# Project_Hackathon_PCB.net
KiCad netlist of a schematic drawn in EasyEDA Pro
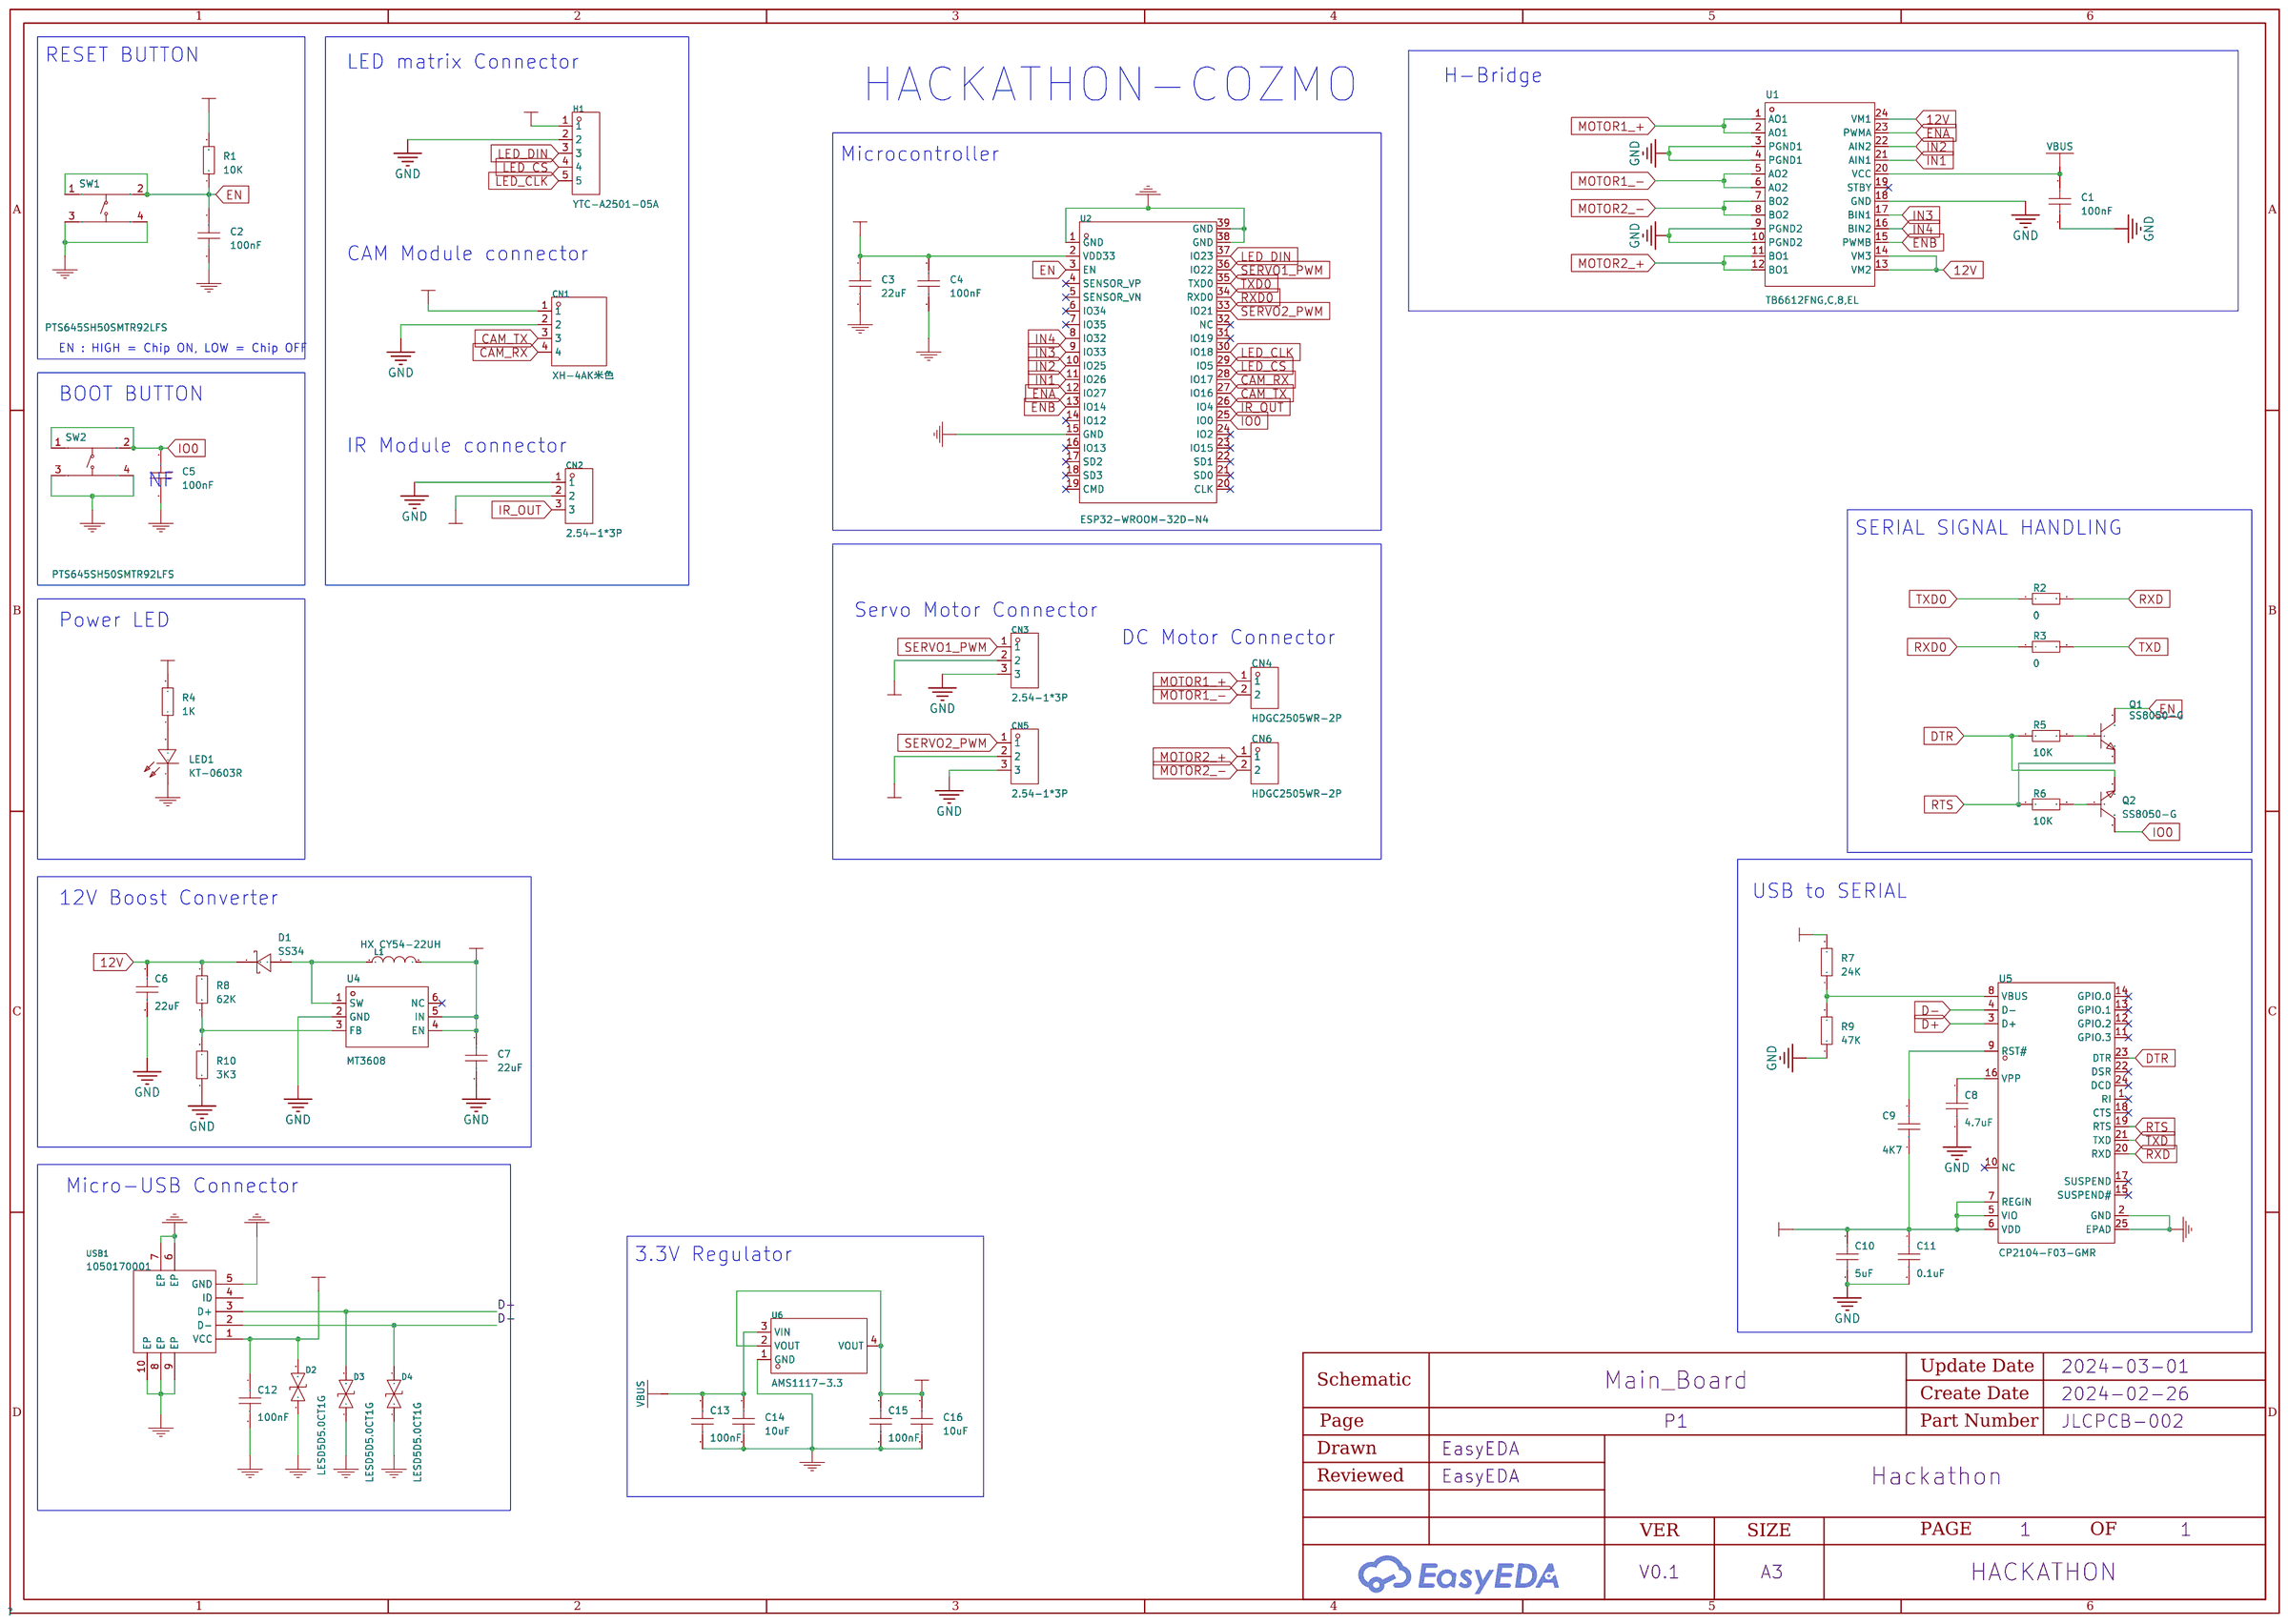
[diagram p0: schematic sheet]

(export (version "E")
  (design (tool "Eeschema 10.0.6"))
  (components
    (comp (ref "C1")
      (value "100nF")
      (footprint "easyedapro:C0603")
      (libsource (lib "easyedapro") (part "CAP"))
    )
    (comp (ref "C2")
      (value "100nF")
      (footprint "easyedapro:C0603")
      (libsource (lib "easyedapro") (part "CAP"))
    )
    (comp (ref "C3")
      (value "22uF")
      (footprint "easyedapro:C0603")
      (libsource (lib "easyedapro") (part "CAP"))
    )
    (comp (ref "C4")
      (value "100nF")
      (footprint "easyedapro:C0603")
      (libsource (lib "easyedapro") (part "CAP"))
    )
    (comp (ref "C5")
      (value "100nF")
      (footprint "easyedapro:C0603")
      (libsource (lib "easyedapro") (part "CAP"))
    )
    (comp (ref "C6")
      (value "22uF")
      (footprint "easyedapro:C0603")
      (libsource (lib "easyedapro") (part "CAP"))
    )
    (comp (ref "C7")
      (value "22uF")
      (footprint "easyedapro:C0603")
      (libsource (lib "easyedapro") (part "CAP"))
    )
    (comp (ref "C8")
      (value "4.7uF")
      (footprint "easyedapro:C0603")
      (libsource (lib "easyedapro") (part "CAP"))
    )
    (comp (ref "C9") (value "4K7") (footprint "easyedapro:C0603") (libsource (lib "easyedapro") (part "CAP")))
    (comp (ref "C10")
      (value "5uF")
      (footprint "easyedapro:C0603")
      (libsource (lib "easyedapro") (part "CAP"))
    )
    (comp (ref "C11")
      (value "0.1uF")
      (footprint "easyedapro:C0603")
      (libsource (lib "easyedapro") (part "CAP"))
    )
    (comp (ref "C12")
      (value "100nF")
      (footprint "easyedapro:C0603")
      (libsource (lib "easyedapro") (part "CAP"))
    )
    (comp (ref "C13")
      (value "100nF")
      (footprint "easyedapro:C0603")
      (libsource (lib "easyedapro") (part "CAP"))
    )
    (comp (ref "C14")
      (value "10uF")
      (footprint "easyedapro:C0603")
      (libsource (lib "easyedapro") (part "CAP"))
    )
    (comp (ref "C15")
      (value "100nF")
      (footprint "easyedapro:C0603")
      (libsource (lib "easyedapro") (part "CAP"))
    )
    (comp (ref "C16")
      (value "10uF")
      (footprint "easyedapro:C0603")
      (libsource (lib "easyedapro") (part "CAP"))
    )
    (comp (ref "CN1")
      (value "XH-4AK米色")
      (footprint "easyedapro:CONN-TH_4P-P2.50_XH-4A")
      (fields (field (name "Manufacturer") "BOOMELE(博穆精密)"))
      (libsource (lib "easyedapro") (part "XH-4AK M"))
    )
    (comp (ref "CN2")
      (value "2.54-1*3P")
      (footprint "easyedapro:CONN-TH_C722693")
      (fields (field (name "Manufacturer") "CAX(创都)"))
      (libsource (lib "easyedapro") (part "2.54-1*3P"))
    )
    (comp (ref "CN3")
      (value "2.54-1*3P")
      (footprint "easyedapro:CONN-TH_C722693")
      (fields (field (name "Manufacturer") "CAX(创都)"))
      (libsource (lib "easyedapro") (part "2.54-1*3P"))
    )
    (comp (ref "CN4")
      (value "HDGC2505WR-2P")
      (footprint "easyedapro:CONN-TH_HDGC2505WR-2P")
      (fields (field (name "Manufacturer") "HDGC(华德共创)"))
      (libsource (lib "easyedapro") (part "HDGC2505WR-2P"))
    )
    (comp (ref "CN5")
      (value "2.54-1*3P")
      (footprint "easyedapro:CONN-TH_C722693")
      (fields (field (name "Manufacturer") "CAX(创都)"))
      (libsource (lib "easyedapro") (part "2.54-1*3P"))
    )
    (comp (ref "CN6")
      (value "HDGC2505WR-2P")
      (footprint "easyedapro:CONN-TH_HDGC2505WR-2P")
      (fields (field (name "Manufacturer") "HDGC(华德共创)"))
      (libsource (lib "easyedapro") (part "HDGC2505WR-2P"))
    )
    (comp (ref "D1")
      (value "SS34")
      (footprint "easyedapro:SMC_L6.9-W5.9-LS7.9-RD")
      (description "Forward Voltage (Vf@If):500mV@3A Reverse Voltage (Vr):40V Average Rectified Current (Io):3A")
      (libsource (lib "easyedapro") (part "SS34_C169162"))
    )
    (comp (ref "D2")
      (value "LESD5D5.0CT1G")
      (footprint "easyedapro:SOD-523_L1.2-W0.8-LS1.6-BI")
      (fields (field (name "Manufacturer") "LRC(乐山无线电)"))
      (libsource (lib "easyedapro") (part "LESD5D5.0CT1G"))
    )
    (comp (ref "D3")
      (value "LESD5D5.0CT1G")
      (footprint "easyedapro:SOD-523_L1.2-W0.8-LS1.6-BI")
      (fields (field (name "Manufacturer") "LRC(乐山无线电)"))
      (libsource (lib "easyedapro") (part "LESD5D5.0CT1G"))
    )
    (comp (ref "D4")
      (value "LESD5D5.0CT1G")
      (footprint "easyedapro:SOD-523_L1.2-W0.8-LS1.6-BI")
      (fields (field (name "Manufacturer") "LRC(乐山无线电)"))
      (libsource (lib "easyedapro") (part "LESD5D5.0CT1G"))
    )
    (comp (ref "H1")
      (value "YTC-A2501-05A")
      (footprint "easyedapro:HDR-TH_5P-P2.50-V-F-2")
      (fields (field (name "Manufacturer") "YIYUAN(怡远)"))
      (libsource (lib "easyedapro") (part "YTC-A2501-05A"))
    )
    (comp (ref "L1")
      (value "HX CY54-22UH")
      (footprint "easyedapro:IND-SMD_L5.8-W5.2_SLF05XX")
      (fields (field (name "Manufacturer") "hanxia(韩下)"))
      (libsource (lib "easyedapro") (part "HX CY54-22UH"))
    )
    (comp (ref "LED1")
      (value "KT-0603R")
      (footprint "easyedapro:LED0603-RD")
      (fields (field (name "Manufacturer") "KENTO"))
      (libsource (lib "easyedapro") (part "KT-0603R"))
    )
    (comp (ref "Q1")
      (value "SS8050-G")
      (footprint "easyedapro:SOT-23-3_L2.9-W1.3-P1.90-LS2.4-BR")
      (fields (field (name "Manufacturer") "CJ(江苏长电/长晶)"))
      (libsource (lib "easyedapro") (part "SS8050-G_C164885"))
    )
    (comp (ref "Q2")
      (value "SS8050-G")
      (footprint "easyedapro:SOT-23-3_L2.9-W1.3-P1.90-LS2.4-BR")
      (fields (field (name "Manufacturer") "CJ(江苏长电/长晶)"))
      (libsource (lib "easyedapro") (part "SS8050-G_C164885"))
    )
    (comp (ref "R1") (value "10K") (footprint "easyedapro:R0603") (libsource (lib "easyedapro") (part "Res")))
    (comp (ref "R2") (value "0") (footprint "easyedapro:R0603") (libsource (lib "easyedapro") (part "Res")))
    (comp (ref "R3") (value "0") (footprint "easyedapro:R0603") (libsource (lib "easyedapro") (part "Res")))
    (comp (ref "R4") (value "1K") (footprint "easyedapro:R0603") (libsource (lib "easyedapro") (part "Res")))
    (comp (ref "R5") (value "10K") (footprint "easyedapro:R0603") (libsource (lib "easyedapro") (part "Res")))
    (comp (ref "R6") (value "10K") (footprint "easyedapro:R0603") (libsource (lib "easyedapro") (part "Res")))
    (comp (ref "R7") (value "24K") (footprint "easyedapro:R0603") (libsource (lib "easyedapro") (part "Res")))
    (comp (ref "R8") (value "62K") (footprint "easyedapro:R0603") (libsource (lib "easyedapro") (part "Res")))
    (comp (ref "R9") (value "47K") (footprint "easyedapro:R0603") (libsource (lib "easyedapro") (part "Res")))
    (comp (ref "R10")
      (value "3K3")
      (footprint "easyedapro:R0603")
      (libsource (lib "easyedapro") (part "Res"))
    )
    (comp (ref "SW1")
      (value "PTS645SH50SMTR92LFS")
      (footprint "easyedapro:KEY-SMD_4P-L6.0-W6.0-P4.50-LS9.0")
      (fields (field (name "Manufacturer") "C&K"))
      (libsource (lib "easyedapro") (part "PTS645SH50SMTR92LFS"))
    )
    (comp (ref "SW2")
      (value "PTS645SH50SMTR92LFS")
      (footprint "easyedapro:KEY-SMD_4P-L6.0-W6.0-P4.50-LS9.0")
      (fields (field (name "Manufacturer") "C&K"))
      (libsource (lib "easyedapro") (part "PTS645SH50SMTR92LFS"))
    )
    (comp (ref "U1")
      (value "TB6612FNG,C,8,EL")
      (footprint "easyedapro:SSOP-24_L8.3-W5.6-P0.65-LS7.6-BL")
      (fields (field (name "Manufacturer") "TOSHIBA(东芝)"))
      (libsource (lib "easyedapro") (part "TB6612FNG,C,8,EL"))
    )
    (comp (ref "U2")
      (value "ESP32-WROOM-32D-N4")
      (footprint "easyedapro:WIFIM-SMD_39P-L25.5-W18.0-P1.27-BL")
      (fields (field (name "Manufacturer") "ESPRESSIF(乐鑫)"))
      (libsource (lib "easyedapro") (part "ESP32-WROOM-32D"))
    )
    (comp (ref "U4")
      (value "MT3608")
      (footprint "easyedapro:SOT-23-6_L2.9-W1.6-P0.95-LS2.8-BL")
      (fields (field (name "Manufacturer") "西安航天民芯"))
      (libsource (lib "easyedapro") (part "MT3608"))
    )
    (comp (ref "U5")
      (value "CP2104-F03-GMR")
      (footprint "easyedapro:QFN-24_L4.0-W4.0-P0.50-BL-EP2.7")
      (fields (field (name "Manufacturer") "SKYWORKS/SILICON LABS(芯科)"))
      (libsource (lib "easyedapro") (part "CP2104-F03-GM"))
    )
    (comp (ref "U6")
      (value "AMS1117-3.3")
      (footprint "easyedapro:SOT-223-3_L6.5-W3.4-P2.30-LS7.0-BR")
      (fields (field (name "Manufacturer") "AMS"))
      (libsource (lib "easyedapro") (part "AMS1117-3.3"))
    )
    (comp (ref "USB1")
      (value "1050170001")
      (footprint "easyedapro:MICRO-USB-SMD_105017-0001")
      (fields (field (name "Manufacturer") "MOLEX"))
      (libsource (lib "easyedapro") (part "105017-0001"))
    )
  )
  (nets
    (net (code "1") (name "+3V3") (class "Default")
      (node (ref "C10") (pin "1") (pinfunction "1_1") (pintype "input"))
      (node (ref "C11") (pin "1") (pinfunction "1_1") (pintype "input"))
      (node (ref "C15") (pin "1") (pinfunction "1_1") (pintype "input"))
      (node (ref "C16") (pin "1") (pinfunction "1_1") (pintype "input"))
      (node (ref "C3") (pin "1") (pinfunction "1_1") (pintype "input"))
      (node (ref "C4") (pin "1") (pinfunction "1_1") (pintype "input"))
      (node (ref "C9") (pin "1") (pinfunction "1_1") (pintype "input"))
      (node (ref "H1") (pin "1") (pinfunction "1_1") (pintype "input"))
      (node (ref "R1") (pin "2") (pinfunction "2_2") (pintype "input"))
      (node (ref "R4") (pin "2") (pinfunction "2_2") (pintype "input"))
      (node (ref "U2") (pin "2") (pinfunction "VDD33_2") (pintype "input"))
      (node (ref "U5") (pin "5") (pinfunction "VIO_5") (pintype "unspecified"))
      (node (ref "U5") (pin "6") (pinfunction "VDD_6") (pintype "unspecified"))
      (node (ref "U5") (pin "7") (pinfunction "REGIN_7") (pintype "unspecified"))
      (node (ref "U6") (pin "2") (pinfunction "VOUT_2") (pintype "input"))
      (node (ref "U6") (pin "4") (pinfunction "VOUT_4") (pintype "input"))
    )
    (net (code "2") (name "12V") (class "Default")
      (node (ref "C6") (pin "1") (pinfunction "1_1") (pintype "input"))
      (node (ref "D1") (pin "1") (pinfunction "C_1") (pintype "input"))
      (node (ref "R8") (pin "2") (pinfunction "2_2") (pintype "input"))
      (node (ref "U1") (pin "13") (pinfunction "VM2_13") (pintype "input"))
      (node (ref "U1") (pin "14") (pinfunction "VM3_14") (pintype "input"))
      (node (ref "U1") (pin "24") (pinfunction "VM1_24") (pintype "input"))
    )
    (net (code "3") (name "CAM_RX") (class "Default")
      (node (ref "CN1") (pin "4") (pinfunction "4_4") (pintype "input"))
      (node (ref "U2") (pin "28") (pinfunction "IO17_28") (pintype "input"))
    )
    (net (code "4") (name "CAM_TX") (class "Default")
      (node (ref "CN1") (pin "3") (pinfunction "3_3") (pintype "input"))
      (node (ref "U2") (pin "27") (pinfunction "IO16_27") (pintype "input"))
    )
    (net (code "5") (name "D+") (class "Default")
      (node (ref "D3") (pin "2") (pinfunction "2_2") (pintype "input"))
      (node (ref "U5") (pin "3") (pinfunction "D+_3") (pintype "unspecified"))
      (node (ref "USB1") (pin "3") (pinfunction "D+_3") (pintype "input"))
    )
    (net (code "6") (name "D-") (class "Default")
      (node (ref "D4") (pin "2") (pinfunction "2_2") (pintype "input"))
      (node (ref "U5") (pin "4") (pinfunction "D-_4") (pintype "unspecified"))
      (node (ref "USB1") (pin "2") (pinfunction "D-_2") (pintype "input"))
    )
    (net (code "7") (name "DTR") (class "Default")
      (node (ref "Q2") (pin "2") (pinfunction "E_2") (pintype "unspecified"))
      (node (ref "R5") (pin "1") (pinfunction "1_1") (pintype "input"))
      (node (ref "U5") (pin "23") (pinfunction "DTR_23") (pintype "unspecified"))
    )
    (net (code "8") (name "EN") (class "Default")
      (node (ref "C2") (pin "1") (pinfunction "1_1") (pintype "input"))
      (node (ref "Q1") (pin "3") (pinfunction "C_3") (pintype "unspecified"))
      (node (ref "R1") (pin "1") (pinfunction "1_1") (pintype "input"))
      (node (ref "SW1") (pin "1") (pinfunction "1_1") (pintype "input"))
      (node (ref "SW1") (pin "2") (pinfunction "2_2") (pintype "input"))
      (node (ref "U2") (pin "3") (pinfunction "EN_3") (pintype "input"))
    )
    (net (code "9") (name "ENA") (class "Default")
      (node (ref "U1") (pin "23") (pinfunction "PWMA_23") (pintype "input"))
      (node (ref "U2") (pin "12") (pinfunction "IO27_12") (pintype "input"))
    )
    (net (code "10") (name "ENB") (class "Default")
      (node (ref "U1") (pin "15") (pinfunction "PWMB_15") (pintype "input"))
      (node (ref "U2") (pin "13") (pinfunction "IO14_13") (pintype "input"))
    )
    (net (code "11") (name "GND") (class "Default")
      (node (ref "C1") (pin "2") (pinfunction "2_2") (pintype "input"))
      (node (ref "C10") (pin "2") (pinfunction "2_2") (pintype "input"))
      (node (ref "C11") (pin "2") (pinfunction "2_2") (pintype "input"))
      (node (ref "C12") (pin "2") (pinfunction "2_2") (pintype "input"))
      (node (ref "C13") (pin "2") (pinfunction "2_2") (pintype "input"))
      (node (ref "C14") (pin "2") (pinfunction "2_2") (pintype "input"))
      (node (ref "C15") (pin "2") (pinfunction "2_2") (pintype "input"))
      (node (ref "C16") (pin "2") (pinfunction "2_2") (pintype "input"))
      (node (ref "C2") (pin "2") (pinfunction "2_2") (pintype "input"))
      (node (ref "C3") (pin "2") (pinfunction "2_2") (pintype "input"))
      (node (ref "C4") (pin "2") (pinfunction "2_2") (pintype "input"))
      (node (ref "C5") (pin "2") (pinfunction "2_2") (pintype "input"))
      (node (ref "C6") (pin "2") (pinfunction "2_2") (pintype "input"))
      (node (ref "C7") (pin "2") (pinfunction "2_2") (pintype "input"))
      (node (ref "C8") (pin "2") (pinfunction "2_2") (pintype "input"))
      (node (ref "CN1") (pin "2") (pinfunction "2_2") (pintype "input"))
      (node (ref "CN2") (pin "1") (pinfunction "1_1") (pintype "input"))
      (node (ref "CN3") (pin "3") (pinfunction "3_3") (pintype "input"))
      (node (ref "CN5") (pin "3") (pinfunction "3_3") (pintype "input"))
      (node (ref "D2") (pin "1") (pinfunction "1_1") (pintype "input"))
      (node (ref "D3") (pin "1") (pinfunction "1_1") (pintype "input"))
      (node (ref "D4") (pin "1") (pinfunction "1_1") (pintype "input"))
      (node (ref "H1") (pin "2") (pinfunction "2_2") (pintype "input"))
      (node (ref "LED1") (pin "1") (pinfunction "K_1") (pintype "input"))
      (node (ref "R10") (pin "1") (pinfunction "1_1") (pintype "input"))
      (node (ref "R9") (pin "1") (pinfunction "1_1") (pintype "input"))
      (node (ref "SW1") (pin "3") (pinfunction "3_3") (pintype "input"))
      (node (ref "SW1") (pin "4") (pinfunction "4_4") (pintype "input"))
      (node (ref "SW2") (pin "3") (pinfunction "3_3") (pintype "input"))
      (node (ref "SW2") (pin "4") (pinfunction "4_4") (pintype "input"))
      (node (ref "U1") (pin "10") (pinfunction "PGND2_10") (pintype "input"))
      (node (ref "U1") (pin "18") (pinfunction "GND_18") (pintype "input"))
      (node (ref "U1") (pin "3") (pinfunction "PGND1_3") (pintype "input"))
      (node (ref "U1") (pin "4") (pinfunction "PGND1_4") (pintype "input"))
      (node (ref "U1") (pin "9") (pinfunction "PGND2_9") (pintype "input"))
      (node (ref "U2") (pin "1") (pinfunction "GND_1") (pintype "input"))
      (node (ref "U2") (pin "15") (pinfunction "GND_15") (pintype "input"))
      (node (ref "U2") (pin "38") (pinfunction "GND_38") (pintype "input"))
      (node (ref "U2") (pin "39") (pinfunction "GND_39") (pintype "input"))
      (node (ref "U4") (pin "2") (pinfunction "GND_2") (pintype "input"))
      (node (ref "U5") (pin "2") (pinfunction "GND_2") (pintype "unspecified"))
      (node (ref "U5") (pin "25") (pinfunction "EPAD_25") (pintype "unspecified"))
      (node (ref "U6") (pin "1") (pinfunction "GND_1") (pintype "input"))
      (node (ref "USB1") (pin "10") (pinfunction "EP_10") (pintype "input"))
      (node (ref "USB1") (pin "5") (pinfunction "GND_5") (pintype "input"))
      (node (ref "USB1") (pin "6") (pinfunction "EP_6") (pintype "input"))
      (node (ref "USB1") (pin "7") (pinfunction "EP_7") (pintype "input"))
      (node (ref "USB1") (pin "8") (pinfunction "EP_8") (pintype "input"))
      (node (ref "USB1") (pin "9") (pinfunction "EP_9") (pintype "input"))
    )
    (net (code "12") (name "IN1") (class "Default")
      (node (ref "U1") (pin "21") (pinfunction "AIN1_21") (pintype "input"))
      (node (ref "U2") (pin "11") (pinfunction "IO26_11") (pintype "input"))
    )
    (net (code "13") (name "IN2") (class "Default")
      (node (ref "U1") (pin "22") (pinfunction "AIN2_22") (pintype "input"))
      (node (ref "U2") (pin "10") (pinfunction "IO25_10") (pintype "input"))
    )
    (net (code "14") (name "IN3") (class "Default")
      (node (ref "U1") (pin "17") (pinfunction "BIN1_17") (pintype "input"))
      (node (ref "U2") (pin "9") (pinfunction "IO33_9") (pintype "input"))
    )
    (net (code "15") (name "IN4") (class "Default")
      (node (ref "U1") (pin "16") (pinfunction "BIN2_16") (pintype "input"))
      (node (ref "U2") (pin "8") (pinfunction "IO32_8") (pintype "input"))
    )
    (net (code "16") (name "IO0") (class "Default")
      (node (ref "C5") (pin "1") (pinfunction "1_1") (pintype "input"))
      (node (ref "Q2") (pin "3") (pinfunction "C_3") (pintype "unspecified"))
      (node (ref "SW2") (pin "1") (pinfunction "1_1") (pintype "input"))
      (node (ref "SW2") (pin "2") (pinfunction "2_2") (pintype "input"))
      (node (ref "U2") (pin "25") (pinfunction "IO0_25") (pintype "input"))
    )
    (net (code "17") (name "IR_OUT") (class "Default")
      (node (ref "CN2") (pin "3") (pinfunction "3_3") (pintype "input"))
      (node (ref "U2") (pin "26") (pinfunction "IO4_26") (pintype "input"))
    )
    (net (code "18") (name "LED_CLK") (class "Default")
      (node (ref "H1") (pin "5") (pinfunction "5_5") (pintype "input"))
      (node (ref "U2") (pin "30") (pinfunction "IO18_30") (pintype "input"))
    )
    (net (code "19") (name "LED_CS") (class "Default")
      (node (ref "H1") (pin "4") (pinfunction "4_4") (pintype "input"))
      (node (ref "U2") (pin "29") (pinfunction "IO5_29") (pintype "input"))
    )
    (net (code "20") (name "LED_DIN") (class "Default")
      (node (ref "H1") (pin "3") (pinfunction "3_3") (pintype "input"))
      (node (ref "U2") (pin "37") (pinfunction "IO23_37") (pintype "input"))
    )
    (net (code "21") (name "MOTOR1_+") (class "Default")
      (node (ref "CN4") (pin "1") (pinfunction "1_1") (pintype "unspecified"))
      (node (ref "U1") (pin "1") (pinfunction "AO1_1") (pintype "input"))
      (node (ref "U1") (pin "2") (pinfunction "AO1_2") (pintype "input"))
    )
    (net (code "22") (name "MOTOR1_-") (class "Default")
      (node (ref "CN4") (pin "2") (pinfunction "2_2") (pintype "unspecified"))
      (node (ref "U1") (pin "5") (pinfunction "AO2_5") (pintype "input"))
      (node (ref "U1") (pin "6") (pinfunction "AO2_6") (pintype "input"))
    )
    (net (code "23") (name "MOTOR2_+") (class "Default")
      (node (ref "CN6") (pin "1") (pinfunction "1_1") (pintype "unspecified"))
      (node (ref "U1") (pin "11") (pinfunction "BO1_11") (pintype "input"))
      (node (ref "U1") (pin "12") (pinfunction "BO1_12") (pintype "input"))
    )
    (net (code "24") (name "MOTOR2_-") (class "Default")
      (node (ref "CN6") (pin "2") (pinfunction "2_2") (pintype "unspecified"))
      (node (ref "U1") (pin "7") (pinfunction "BO2_7") (pintype "input"))
      (node (ref "U1") (pin "8") (pinfunction "BO2_8") (pintype "input"))
    )
    (net (code "25") (name "Net-(D1-A)") (class "Default")
      (node (ref "D1") (pin "2") (pinfunction "A_2") (pintype "input"))
      (node (ref "L1") (pin "1") (pinfunction "1_1") (pintype "input"))
      (node (ref "U4") (pin "1") (pinfunction "SW_1") (pintype "input"))
    )
    (net (code "26") (name "Net-(LED1-A)") (class "Default")
      (node (ref "LED1") (pin "2") (pinfunction "A_2") (pintype "input"))
      (node (ref "R4") (pin "1") (pinfunction "1_1") (pintype "input"))
    )
    (net (code "27") (name "Net-(Q1-B)") (class "Default")
      (node (ref "Q1") (pin "1") (pinfunction "B_1") (pintype "unspecified"))
      (node (ref "R5") (pin "2") (pinfunction "2_2") (pintype "input"))
    )
    (net (code "28") (name "Net-(Q2-B)") (class "Default")
      (node (ref "Q2") (pin "1") (pinfunction "B_1") (pintype "unspecified"))
      (node (ref "R6") (pin "2") (pinfunction "2_2") (pintype "input"))
    )
    (net (code "29") (name "Net-(U4-FB)") (class "Default")
      (node (ref "R10") (pin "2") (pinfunction "2_2") (pintype "input"))
      (node (ref "R8") (pin "1") (pinfunction "1_1") (pintype "input"))
      (node (ref "U4") (pin "3") (pinfunction "FB_3") (pintype "input"))
    )
    (net (code "30") (name "Net-(U5-RST#)") (class "Default")
      (node (ref "C9") (pin "2") (pinfunction "2_2") (pintype "input"))
      (node (ref "U5") (pin "9") (pinfunction "RST#_9") (pintype "unspecified"))
    )
    (net (code "31") (name "Net-(U5-VBUS)") (class "Default")
      (node (ref "R7") (pin "1") (pinfunction "1_1") (pintype "input"))
      (node (ref "R9") (pin "2") (pinfunction "2_2") (pintype "input"))
      (node (ref "U5") (pin "8") (pinfunction "VBUS_8") (pintype "unspecified"))
    )
    (net (code "32") (name "Net-(U5-VPP)") (class "Default")
      (node (ref "C8") (pin "1") (pinfunction "1_1") (pintype "input"))
      (node (ref "U5") (pin "16") (pinfunction "VPP_16") (pintype "unspecified"))
    )
    (net (code "33") (name "RTS") (class "Default")
      (node (ref "Q1") (pin "2") (pinfunction "E_2") (pintype "unspecified"))
      (node (ref "R6") (pin "1") (pinfunction "1_1") (pintype "input"))
      (node (ref "U5") (pin "19") (pinfunction "RTS_19") (pintype "unspecified"))
    )
    (net (code "34") (name "RXD") (class "Default")
      (node (ref "R2") (pin "2") (pinfunction "2_2") (pintype "input"))
      (node (ref "U5") (pin "20") (pinfunction "RXD_20") (pintype "unspecified"))
    )
    (net (code "35") (name "RXD0") (class "Default")
      (node (ref "R3") (pin "1") (pinfunction "1_1") (pintype "input"))
      (node (ref "U2") (pin "34") (pinfunction "RXD0_34") (pintype "input"))
    )
    (net (code "36") (name "SERVO1_PWM") (class "Default")
      (node (ref "CN3") (pin "1") (pinfunction "1_1") (pintype "input"))
      (node (ref "U2") (pin "36") (pinfunction "IO22_36") (pintype "input"))
    )
    (net (code "37") (name "SERVO2_PWM") (class "Default")
      (node (ref "CN5") (pin "1") (pinfunction "1_1") (pintype "input"))
      (node (ref "U2") (pin "33") (pinfunction "IO21_33") (pintype "input"))
    )
    (net (code "38") (name "TXD") (class "Default")
      (node (ref "R3") (pin "2") (pinfunction "2_2") (pintype "input"))
      (node (ref "U5") (pin "21") (pinfunction "TXD_21") (pintype "unspecified"))
    )
    (net (code "39") (name "TXD0") (class "Default")
      (node (ref "R2") (pin "1") (pinfunction "1_1") (pintype "input"))
      (node (ref "U2") (pin "35") (pinfunction "TXD0_35") (pintype "input"))
    )
    (net (code "40") (name "VBUS") (class "Default")
      (node (ref "C1") (pin "1") (pinfunction "1_1") (pintype "input"))
      (node (ref "C12") (pin "1") (pinfunction "1_1") (pintype "input"))
      (node (ref "C13") (pin "1") (pinfunction "1_1") (pintype "input"))
      (node (ref "C14") (pin "1") (pinfunction "1_1") (pintype "input"))
      (node (ref "C7") (pin "1") (pinfunction "1_1") (pintype "input"))
      (node (ref "CN1") (pin "1") (pinfunction "1_1") (pintype "input"))
      (node (ref "CN2") (pin "2") (pinfunction "2_2") (pintype "input"))
      (node (ref "CN3") (pin "2") (pinfunction "2_2") (pintype "input"))
      (node (ref "CN5") (pin "2") (pinfunction "2_2") (pintype "input"))
      (node (ref "D2") (pin "2") (pinfunction "2_2") (pintype "input"))
      (node (ref "L1") (pin "2") (pinfunction "2_2") (pintype "input"))
      (node (ref "R7") (pin "2") (pinfunction "2_2") (pintype "input"))
      (node (ref "U1") (pin "20") (pinfunction "VCC_20") (pintype "input"))
      (node (ref "U4") (pin "4") (pinfunction "EN_4") (pintype "input"))
      (node (ref "U4") (pin "5") (pinfunction "IN_5") (pintype "input"))
      (node (ref "U6") (pin "3") (pinfunction "VIN_3") (pintype "input"))
      (node (ref "USB1") (pin "1") (pinfunction "VCC_1") (pintype "input"))
    )
    (net (code "41") (name "unconnected-(U1-STBY-Pad19)") (class "Default")
      (node (ref "U1") (pin "19") (pinfunction "STBY_19") (pintype "input+no_connect"))
    )
    (net (code "42") (name "unconnected-(U2-CLK-Pad20)") (class "Default")
      (node (ref "U2") (pin "20") (pinfunction "CLK_20") (pintype "input+no_connect"))
    )
    (net (code "43") (name "unconnected-(U2-CMD-Pad19)") (class "Default")
      (node (ref "U2") (pin "19") (pinfunction "CMD_19") (pintype "input+no_connect"))
    )
    (net (code "44") (name "unconnected-(U2-IO2-Pad24)") (class "Default")
      (node (ref "U2") (pin "24") (pinfunction "IO2_24") (pintype "input+no_connect"))
    )
    (net (code "45") (name "unconnected-(U2-IO12-Pad14)") (class "Default")
      (node (ref "U2") (pin "14") (pinfunction "IO12_14") (pintype "input+no_connect"))
    )
    (net (code "46") (name "unconnected-(U2-IO13-Pad16)") (class "Default")
      (node (ref "U2") (pin "16") (pinfunction "IO13_16") (pintype "input+no_connect"))
    )
    (net (code "47") (name "unconnected-(U2-IO15-Pad23)") (class "Default")
      (node (ref "U2") (pin "23") (pinfunction "IO15_23") (pintype "input+no_connect"))
    )
    (net (code "48") (name "unconnected-(U2-IO19-Pad31)") (class "Default")
      (node (ref "U2") (pin "31") (pinfunction "IO19_31") (pintype "input+no_connect"))
    )
    (net (code "49") (name "unconnected-(U2-IO34-Pad6)") (class "Default")
      (node (ref "U2") (pin "6") (pinfunction "IO34_6") (pintype "input+no_connect"))
    )
    (net (code "50") (name "unconnected-(U2-IO35-Pad7)") (class "Default")
      (node (ref "U2") (pin "7") (pinfunction "IO35_7") (pintype "input+no_connect"))
    )
    (net (code "51") (name "unconnected-(U2-NC-Pad32)") (class "Default")
      (node (ref "U2") (pin "32") (pinfunction "NC_32") (pintype "input+no_connect"))
    )
    (net (code "52") (name "unconnected-(U2-SD0-Pad21)") (class "Default")
      (node (ref "U2") (pin "21") (pinfunction "SD0_21") (pintype "input+no_connect"))
    )
    (net (code "53") (name "unconnected-(U2-SD1-Pad22)") (class "Default")
      (node (ref "U2") (pin "22") (pinfunction "SD1_22") (pintype "input+no_connect"))
    )
    (net (code "54") (name "unconnected-(U2-SD2-Pad17)") (class "Default")
      (node (ref "U2") (pin "17") (pinfunction "SD2_17") (pintype "input+no_connect"))
    )
    (net (code "55") (name "unconnected-(U2-SD3-Pad18)") (class "Default")
      (node (ref "U2") (pin "18") (pinfunction "SD3_18") (pintype "input+no_connect"))
    )
    (net (code "56") (name "unconnected-(U2-SENSOR_VN-Pad5)") (class "Default")
      (node (ref "U2") (pin "5") (pinfunction "SENSOR_VN_5") (pintype "input+no_connect"))
    )
    (net (code "57") (name "unconnected-(U2-SENSOR_VP-Pad4)") (class "Default")
      (node (ref "U2") (pin "4") (pinfunction "SENSOR_VP_4") (pintype "input+no_connect"))
    )
    (net (code "58") (name "unconnected-(U4-NC-Pad6)") (class "Default")
      (node (ref "U4") (pin "6") (pinfunction "NC_6") (pintype "input+no_connect"))
    )
    (net (code "59") (name "unconnected-(U5-CTS-Pad18)") (class "Default")
      (node (ref "U5") (pin "18") (pinfunction "CTS_18") (pintype "unspecified+no_connect"))
    )
    (net (code "60") (name "unconnected-(U5-DCD-Pad24)") (class "Default")
      (node (ref "U5") (pin "24") (pinfunction "DCD_24") (pintype "unspecified+no_connect"))
    )
    (net (code "61") (name "unconnected-(U5-DSR-Pad22)") (class "Default")
      (node (ref "U5") (pin "22") (pinfunction "DSR_22") (pintype "unspecified+no_connect"))
    )
    (net (code "62") (name "unconnected-(U5-GPIO.0-Pad14)") (class "Default")
      (node (ref "U5") (pin "14") (pinfunction "GPIO.0_14") (pintype "unspecified+no_connect"))
    )
    (net (code "63") (name "unconnected-(U5-GPIO.1-Pad13)") (class "Default")
      (node (ref "U5") (pin "13") (pinfunction "GPIO.1_13") (pintype "unspecified+no_connect"))
    )
    (net (code "64") (name "unconnected-(U5-GPIO.2-Pad12)") (class "Default")
      (node (ref "U5") (pin "12") (pinfunction "GPIO.2_12") (pintype "unspecified+no_connect"))
    )
    (net (code "65") (name "unconnected-(U5-GPIO.3-Pad11)") (class "Default")
      (node (ref "U5") (pin "11") (pinfunction "GPIO.3_11") (pintype "unspecified+no_connect"))
    )
    (net (code "66") (name "unconnected-(U5-NC-Pad10)") (class "Default")
      (node (ref "U5") (pin "10") (pinfunction "NC_10") (pintype "unspecified+no_connect"))
    )
    (net (code "67") (name "unconnected-(U5-RI-Pad1)") (class "Default")
      (node (ref "U5") (pin "1") (pinfunction "RI_1") (pintype "unspecified+no_connect"))
    )
    (net (code "68") (name "unconnected-(U5-SUSPEND#-Pad15)") (class "Default")
      (node (ref "U5") (pin "15") (pinfunction "SUSPEND#_15") (pintype "unspecified+no_connect"))
    )
    (net (code "69") (name "unconnected-(U5-SUSPEND-Pad17)") (class "Default")
      (node (ref "U5") (pin "17") (pinfunction "SUSPEND_17") (pintype "unspecified+no_connect"))
    )
    (net (code "70") (name "unconnected-(USB1-ID-Pad4)") (class "Default")
      (node (ref "USB1") (pin "4") (pinfunction "ID_4") (pintype "input"))
    )
  )
)
